# 7ch_op_amp_board_v41.net
KiCad netlist of a schematic drawn in EAGLE
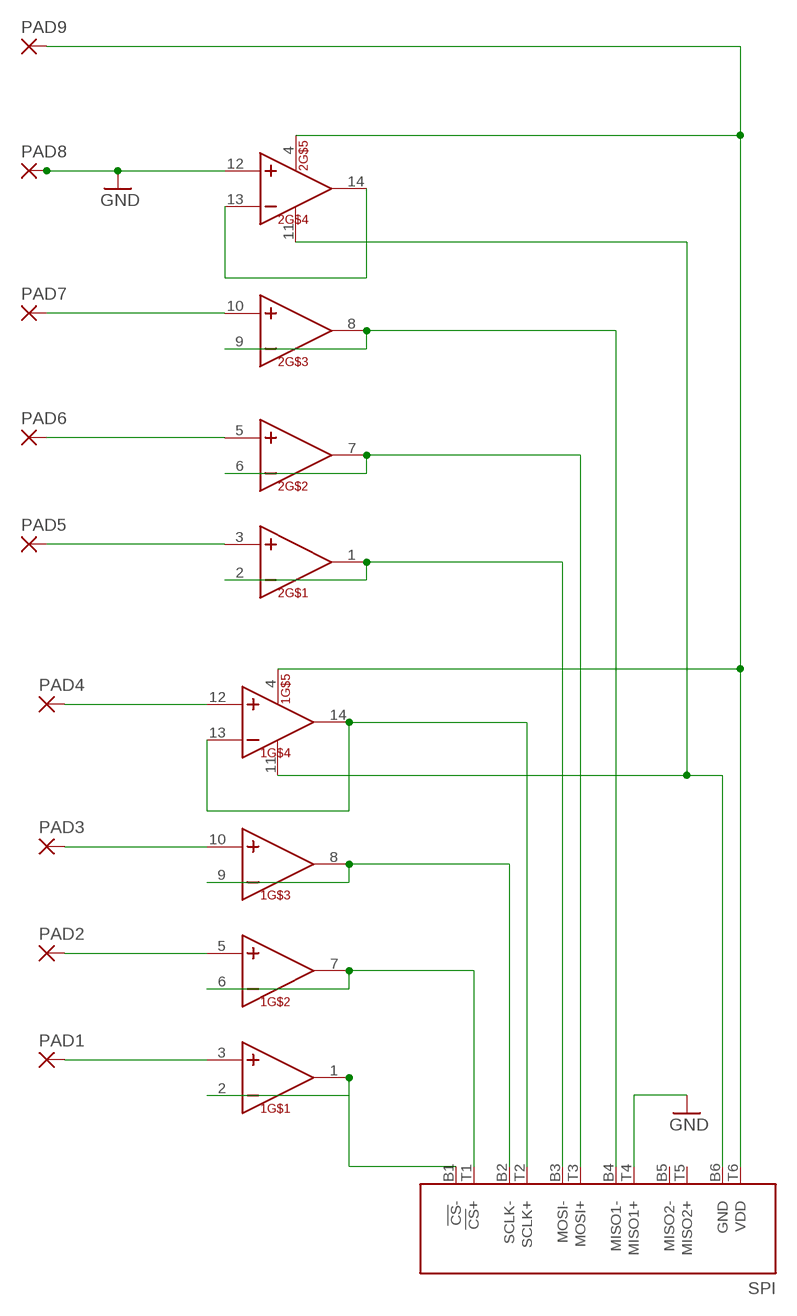
[diagram p0: schematic, sheet 1]

(export (version "E")
  (design (tool "Eeschema 10.0.6"))
  (components
    (comp (ref "1")
      (value "TL074-TSSOP")
      (footprint "eagle-import:TSSOP14")
      (libsource (lib "eagle-import") (part "TL074-TSSOP"))
    )
    (comp (ref "2")
      (value "TL074-TSSOP")
      (footprint "eagle-import:TSSOP14")
      (libsource (lib "eagle-import") (part "TL074-TSSOP"))
    )
    (comp (ref "PAD1")
      (value "1,6/0,9")
      (footprint "eagle-import:1,6_0,9")
      (libsource (lib "eagle-import") (part "1,6/0,9"))
    )
    (comp (ref "PAD2")
      (value "1,6/0,9")
      (footprint "eagle-import:1,6_0,9")
      (libsource (lib "eagle-import") (part "1,6/0,9"))
    )
    (comp (ref "PAD3")
      (value "1,6/0,9")
      (footprint "eagle-import:1,6_0,9")
      (libsource (lib "eagle-import") (part "1,6/0,9"))
    )
    (comp (ref "PAD4")
      (value "1,6/0,9")
      (footprint "eagle-import:1,6_0,9")
      (libsource (lib "eagle-import") (part "1,6/0,9"))
    )
    (comp (ref "PAD5")
      (value "1,6/0,9")
      (footprint "eagle-import:1,6_0,9")
      (libsource (lib "eagle-import") (part "1,6/0,9"))
    )
    (comp (ref "PAD6")
      (value "1,6/0,9")
      (footprint "eagle-import:1,6_0,9")
      (libsource (lib "eagle-import") (part "1,6/0,9"))
    )
    (comp (ref "PAD7")
      (value "1,6/0,9")
      (footprint "eagle-import:1,6_0,9")
      (libsource (lib "eagle-import") (part "1,6/0,9"))
    )
    (comp (ref "PAD8")
      (value "1,6/0,9")
      (footprint "eagle-import:1,6_0,9")
      (libsource (lib "eagle-import") (part "1,6/0,9"))
    )
    (comp (ref "PAD9")
      (value "1,6/0,9")
      (footprint "eagle-import:1,6_0,9")
      (libsource (lib "eagle-import") (part "1,6/0,9"))
    )
    (comp (ref "SPI")
      (value "RHD2000-CABLE-AMP-SIDE")
      (footprint "eagle-import:OMNETICS_PZN-12-AA")
      (libsource (lib "eagle-import") (part "RHD2000-CABLE-AMP-SIDE"))
    )
  )
  (nets
    (net (code "1") (name "GND") (class "Default")
      (node (ref "2") (pin "12") (pinfunction "IN+_12") (pintype "input"))
      (node (ref "PAD8") (pin "1") (pinfunction "P_1") (pintype "passive"))
      (node (ref "SPI") (pin "T4") (pinfunction "MISO1+_T4") (pintype "bidirectional"))
    )
    (net (code "2") (name "Net-(1A-IN+)") (class "Default")
      (node (ref "1") (pin "3") (pinfunction "IN+_3") (pintype "input"))
      (node (ref "PAD1") (pin "1") (pinfunction "P_1") (pintype "passive"))
    )
    (net (code "3") (name "Net-(1A-IN-)") (class "Default")
      (node (ref "1") (pin "1") (pinfunction "OUT_1") (pintype "output"))
      (node (ref "1") (pin "2") (pinfunction "IN-_2") (pintype "input"))
      (node (ref "SPI") (pin "B1") (pinfunction "~{CS}-_B1") (pintype "bidirectional"))
    )
    (net (code "4") (name "Net-(1B-IN+)") (class "Default")
      (node (ref "1") (pin "5") (pinfunction "IN+_5") (pintype "input"))
      (node (ref "PAD2") (pin "1") (pinfunction "P_1") (pintype "passive"))
    )
    (net (code "5") (name "Net-(1B-IN-)") (class "Default")
      (node (ref "1") (pin "6") (pinfunction "IN-_6") (pintype "input"))
      (node (ref "1") (pin "7") (pinfunction "OUT_7") (pintype "output"))
      (node (ref "SPI") (pin "T1") (pinfunction "~{CS}+_T1") (pintype "bidirectional"))
    )
    (net (code "6") (name "Net-(1C-IN+)") (class "Default")
      (node (ref "1") (pin "10") (pinfunction "IN+_10") (pintype "input"))
      (node (ref "PAD3") (pin "1") (pinfunction "P_1") (pintype "passive"))
    )
    (net (code "7") (name "Net-(1C-IN-)") (class "Default")
      (node (ref "1") (pin "8") (pinfunction "OUT_8") (pintype "output"))
      (node (ref "1") (pin "9") (pinfunction "IN-_9") (pintype "input"))
      (node (ref "SPI") (pin "B2") (pinfunction "SCLK-_B2") (pintype "bidirectional"))
    )
    (net (code "8") (name "Net-(1D-IN+)") (class "Default")
      (node (ref "1") (pin "12") (pinfunction "IN+_12") (pintype "input"))
      (node (ref "PAD4") (pin "1") (pinfunction "P_1") (pintype "passive"))
    )
    (net (code "9") (name "Net-(1D-IN-)") (class "Default")
      (node (ref "1") (pin "13") (pinfunction "IN-_13") (pintype "input"))
      (node (ref "1") (pin "14") (pinfunction "OUT_14") (pintype "output"))
      (node (ref "SPI") (pin "T2") (pinfunction "SCLK+_T2") (pintype "bidirectional"))
    )
    (net (code "10") (name "Net-(1E-VCC+)") (class "Default")
      (node (ref "1") (pin "4") (pinfunction "VCC+_4") (pintype "power_in"))
      (node (ref "2") (pin "4") (pinfunction "VCC+_4") (pintype "power_in"))
      (node (ref "PAD9") (pin "1") (pinfunction "P_1") (pintype "passive"))
      (node (ref "SPI") (pin "T6") (pinfunction "VDD_T6") (pintype "bidirectional"))
    )
    (net (code "11") (name "Net-(1E-VCC-)") (class "Default")
      (node (ref "1") (pin "11") (pinfunction "VCC-_11") (pintype "power_in"))
      (node (ref "2") (pin "11") (pinfunction "VCC-_11") (pintype "power_in"))
      (node (ref "SPI") (pin "B6") (pinfunction "GND_B6") (pintype "power_in"))
    )
    (net (code "12") (name "Net-(2A-IN+)") (class "Default")
      (node (ref "2") (pin "3") (pinfunction "IN+_3") (pintype "input"))
      (node (ref "PAD5") (pin "1") (pinfunction "P_1") (pintype "passive"))
    )
    (net (code "13") (name "Net-(2A-IN-)") (class "Default")
      (node (ref "2") (pin "1") (pinfunction "OUT_1") (pintype "output"))
      (node (ref "2") (pin "2") (pinfunction "IN-_2") (pintype "input"))
      (node (ref "SPI") (pin "B3") (pinfunction "MOSI-_B3") (pintype "bidirectional"))
    )
    (net (code "14") (name "Net-(2B-IN+)") (class "Default")
      (node (ref "2") (pin "5") (pinfunction "IN+_5") (pintype "input"))
      (node (ref "PAD6") (pin "1") (pinfunction "P_1") (pintype "passive"))
    )
    (net (code "15") (name "Net-(2B-IN-)") (class "Default")
      (node (ref "2") (pin "6") (pinfunction "IN-_6") (pintype "input"))
      (node (ref "2") (pin "7") (pinfunction "OUT_7") (pintype "output"))
      (node (ref "SPI") (pin "T3") (pinfunction "MOSI+_T3") (pintype "bidirectional"))
    )
    (net (code "16") (name "Net-(2C-IN+)") (class "Default")
      (node (ref "2") (pin "10") (pinfunction "IN+_10") (pintype "input"))
      (node (ref "PAD7") (pin "1") (pinfunction "P_1") (pintype "passive"))
    )
    (net (code "17") (name "Net-(2C-IN-)") (class "Default")
      (node (ref "2") (pin "8") (pinfunction "OUT_8") (pintype "output"))
      (node (ref "2") (pin "9") (pinfunction "IN-_9") (pintype "input"))
      (node (ref "SPI") (pin "B4") (pinfunction "MISO1-_B4") (pintype "bidirectional"))
    )
    (net (code "18") (name "Net-(2D-IN-)") (class "Default")
      (node (ref "2") (pin "13") (pinfunction "IN-_13") (pintype "input"))
      (node (ref "2") (pin "14") (pinfunction "OUT_14") (pintype "output"))
    )
    (net (code "19") (name "unconnected-(SPI-MISO2+-PadT5)") (class "Default")
      (node (ref "SPI") (pin "T5") (pinfunction "MISO2+_T5") (pintype "bidirectional"))
    )
    (net (code "20") (name "unconnected-(SPI-MISO2--PadB5)") (class "Default")
      (node (ref "SPI") (pin "B5") (pinfunction "MISO2-_B5") (pintype "bidirectional"))
    )
  )
)
